# basic-demodulator.net
KiCad netlist of a schematic drawn in EAGLE
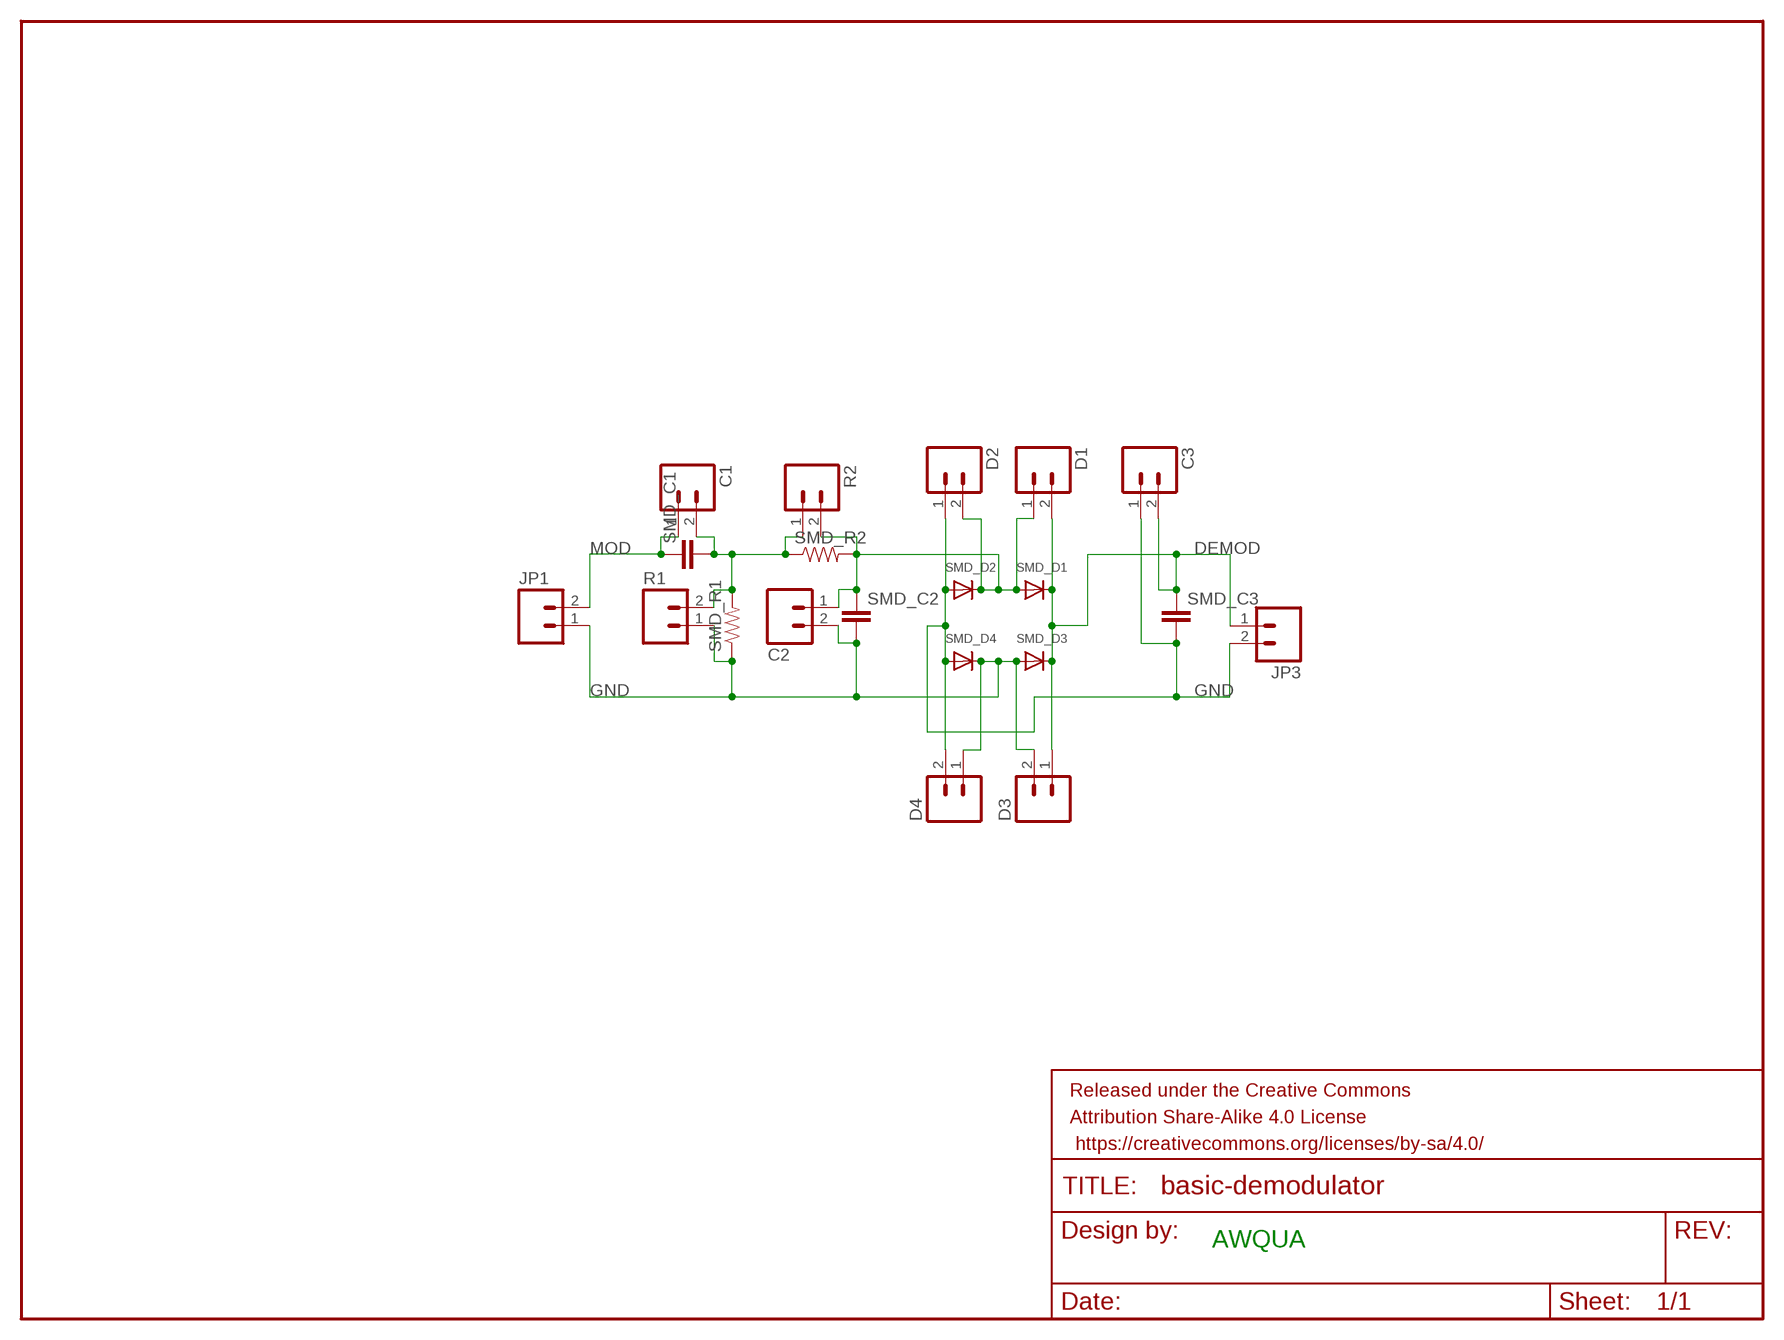
[diagram p0: schematic, sheet 1]

(export (version "E")
  (design (tool "Eeschema 10.0.6"))
  (components
    (comp (ref "C1")
      (value "M02PTH")
      (footprint "eagle-import:1X02")
      (libsource (lib "eagle-import") (part "M02PTH"))
    )
    (comp (ref "C2")
      (value "M02PTH")
      (footprint "eagle-import:1X02")
      (libsource (lib "eagle-import") (part "M02PTH"))
    )
    (comp (ref "C3")
      (value "M02PTH")
      (footprint "eagle-import:1X02")
      (libsource (lib "eagle-import") (part "M02PTH"))
    )
    (comp (ref "D1")
      (value "M02PTH")
      (footprint "eagle-import:1X02")
      (libsource (lib "eagle-import") (part "M02PTH"))
    )
    (comp (ref "D2")
      (value "M02PTH")
      (footprint "eagle-import:1X02")
      (libsource (lib "eagle-import") (part "M02PTH"))
    )
    (comp (ref "D3")
      (value "M02PTH")
      (footprint "eagle-import:1X02")
      (libsource (lib "eagle-import") (part "M02PTH"))
    )
    (comp (ref "D4")
      (value "M02PTH")
      (footprint "eagle-import:1X02")
      (libsource (lib "eagle-import") (part "M02PTH"))
    )
    (comp (ref "FRAME1")
      (value "FRAME-LETTER")
      (footprint "eagle-import:CREATIVE_COMMONS")
      (libsource (lib "eagle-import") (part "FRAME-LETTER"))
    )
    (comp (ref "JP1")
      (value "M02PTH")
      (footprint "eagle-import:1X02")
      (libsource (lib "eagle-import") (part "M02PTH"))
    )
    (comp (ref "JP3")
      (value "M02PTH")
      (footprint "eagle-import:1X02")
      (libsource (lib "eagle-import") (part "M02PTH"))
    )
    (comp (ref "R1")
      (value "M02PTH")
      (footprint "eagle-import:1X02")
      (libsource (lib "eagle-import") (part "M02PTH"))
    )
    (comp (ref "R2")
      (value "M02PTH")
      (footprint "eagle-import:1X02")
      (libsource (lib "eagle-import") (part "M02PTH"))
    )
    (comp (ref "SMD_C1")
      (value "CAP0603-CAP")
      (footprint "eagle-import:0603-CAP")
      (libsource (lib "eagle-import") (part "CAP0603-CAP"))
    )
    (comp (ref "SMD_C2")
      (value "CAP0603-CAP")
      (footprint "eagle-import:0603-CAP")
      (libsource (lib "eagle-import") (part "CAP0603-CAP"))
    )
    (comp (ref "SMD_C3")
      (value "CAP0603-CAP")
      (footprint "eagle-import:0603-CAP")
      (libsource (lib "eagle-import") (part "CAP0603-CAP"))
    )
    (comp (ref "SMD_D1")
      (value "DIODESOD-123")
      (footprint "eagle-import:SOD-123")
      (libsource (lib "eagle-import") (part "DIODESOD-123"))
    )
    (comp (ref "SMD_D2")
      (value "DIODESOD-123")
      (footprint "eagle-import:SOD-123")
      (libsource (lib "eagle-import") (part "DIODESOD-123"))
    )
    (comp (ref "SMD_D3")
      (value "DIODESOD-123")
      (footprint "eagle-import:SOD-123")
      (libsource (lib "eagle-import") (part "DIODESOD-123"))
    )
    (comp (ref "SMD_D4")
      (value "DIODESOD-123")
      (footprint "eagle-import:SOD-123")
      (libsource (lib "eagle-import") (part "DIODESOD-123"))
    )
    (comp (ref "SMD_R1")
      (value "RESISTOR0603-RES")
      (footprint "eagle-import:0603-RES")
      (libsource (lib "eagle-import") (part "RESISTOR0603-RES"))
    )
    (comp (ref "SMD_R2")
      (value "RESISTOR0603-RES")
      (footprint "eagle-import:0603-RES")
      (libsource (lib "eagle-import") (part "RESISTOR0603-RES"))
    )
  )
  (nets
    (net (code "1") (name "/DEMOD") (class "Default")
      (node (ref "C3") (pin "2") (pinfunction "2_2") (pintype "passive"))
      (node (ref "D1") (pin "2") (pinfunction "2_2") (pintype "passive"))
      (node (ref "D3") (pin "1") (pinfunction "1_1") (pintype "passive"))
      (node (ref "JP3") (pin "1") (pinfunction "1_1") (pintype "passive"))
      (node (ref "SMD_C3") (pin "1") (pinfunction "1_1") (pintype "passive"))
      (node (ref "SMD_D1") (pin "C") (pinfunction "C_C") (pintype "passive"))
      (node (ref "SMD_D3") (pin "C") (pinfunction "C_C") (pintype "passive"))
    )
    (net (code "2") (name "/GND") (class "Default")
      (node (ref "C2") (pin "2") (pinfunction "2_2") (pintype "passive"))
      (node (ref "C3") (pin "1") (pinfunction "1_1") (pintype "passive"))
      (node (ref "D2") (pin "1") (pinfunction "1_1") (pintype "passive"))
      (node (ref "D3") (pin "2") (pinfunction "2_2") (pintype "passive"))
      (node (ref "D4") (pin "1") (pinfunction "1_1") (pintype "passive"))
      (node (ref "D4") (pin "2") (pinfunction "2_2") (pintype "passive"))
      (node (ref "JP1") (pin "1") (pinfunction "1_1") (pintype "passive"))
      (node (ref "JP3") (pin "2") (pinfunction "2_2") (pintype "passive"))
      (node (ref "R1") (pin "1") (pinfunction "1_1") (pintype "passive"))
      (node (ref "SMD_C2") (pin "2") (pinfunction "2_2") (pintype "passive"))
      (node (ref "SMD_C3") (pin "2") (pinfunction "2_2") (pintype "passive"))
      (node (ref "SMD_D2") (pin "A") (pinfunction "A_A") (pintype "passive"))
      (node (ref "SMD_D3") (pin "A") (pinfunction "A_A") (pintype "passive"))
      (node (ref "SMD_D4") (pin "A") (pinfunction "A_A") (pintype "passive"))
      (node (ref "SMD_D4") (pin "C") (pinfunction "C_C") (pintype "passive"))
      (node (ref "SMD_R1") (pin "1") (pinfunction "1_1") (pintype "passive"))
    )
    (net (code "3") (name "/MOD") (class "Default")
      (node (ref "C1") (pin "1") (pinfunction "1_1") (pintype "passive"))
      (node (ref "JP1") (pin "2") (pinfunction "2_2") (pintype "passive"))
      (node (ref "SMD_C1") (pin "1") (pinfunction "1_1") (pintype "passive"))
    )
    (net (code "4") (name "Net-(C1-Pad2)") (class "Default")
      (node (ref "C1") (pin "2") (pinfunction "2_2") (pintype "passive"))
      (node (ref "R1") (pin "2") (pinfunction "2_2") (pintype "passive"))
      (node (ref "R2") (pin "1") (pinfunction "1_1") (pintype "passive"))
      (node (ref "SMD_C1") (pin "2") (pinfunction "2_2") (pintype "passive"))
      (node (ref "SMD_R1") (pin "2") (pinfunction "2_2") (pintype "passive"))
      (node (ref "SMD_R2") (pin "1") (pinfunction "1_1") (pintype "passive"))
    )
    (net (code "5") (name "Net-(C2-Pad1)") (class "Default")
      (node (ref "C2") (pin "1") (pinfunction "1_1") (pintype "passive"))
      (node (ref "D1") (pin "1") (pinfunction "1_1") (pintype "passive"))
      (node (ref "D2") (pin "2") (pinfunction "2_2") (pintype "passive"))
      (node (ref "R2") (pin "2") (pinfunction "2_2") (pintype "passive"))
      (node (ref "SMD_C2") (pin "1") (pinfunction "1_1") (pintype "passive"))
      (node (ref "SMD_D1") (pin "A") (pinfunction "A_A") (pintype "passive"))
      (node (ref "SMD_D2") (pin "C") (pinfunction "C_C") (pintype "passive"))
      (node (ref "SMD_R2") (pin "2") (pinfunction "2_2") (pintype "passive"))
    )
  )
)
